# MCU.net
KiCad netlist of a schematic drawn in Altium Designer
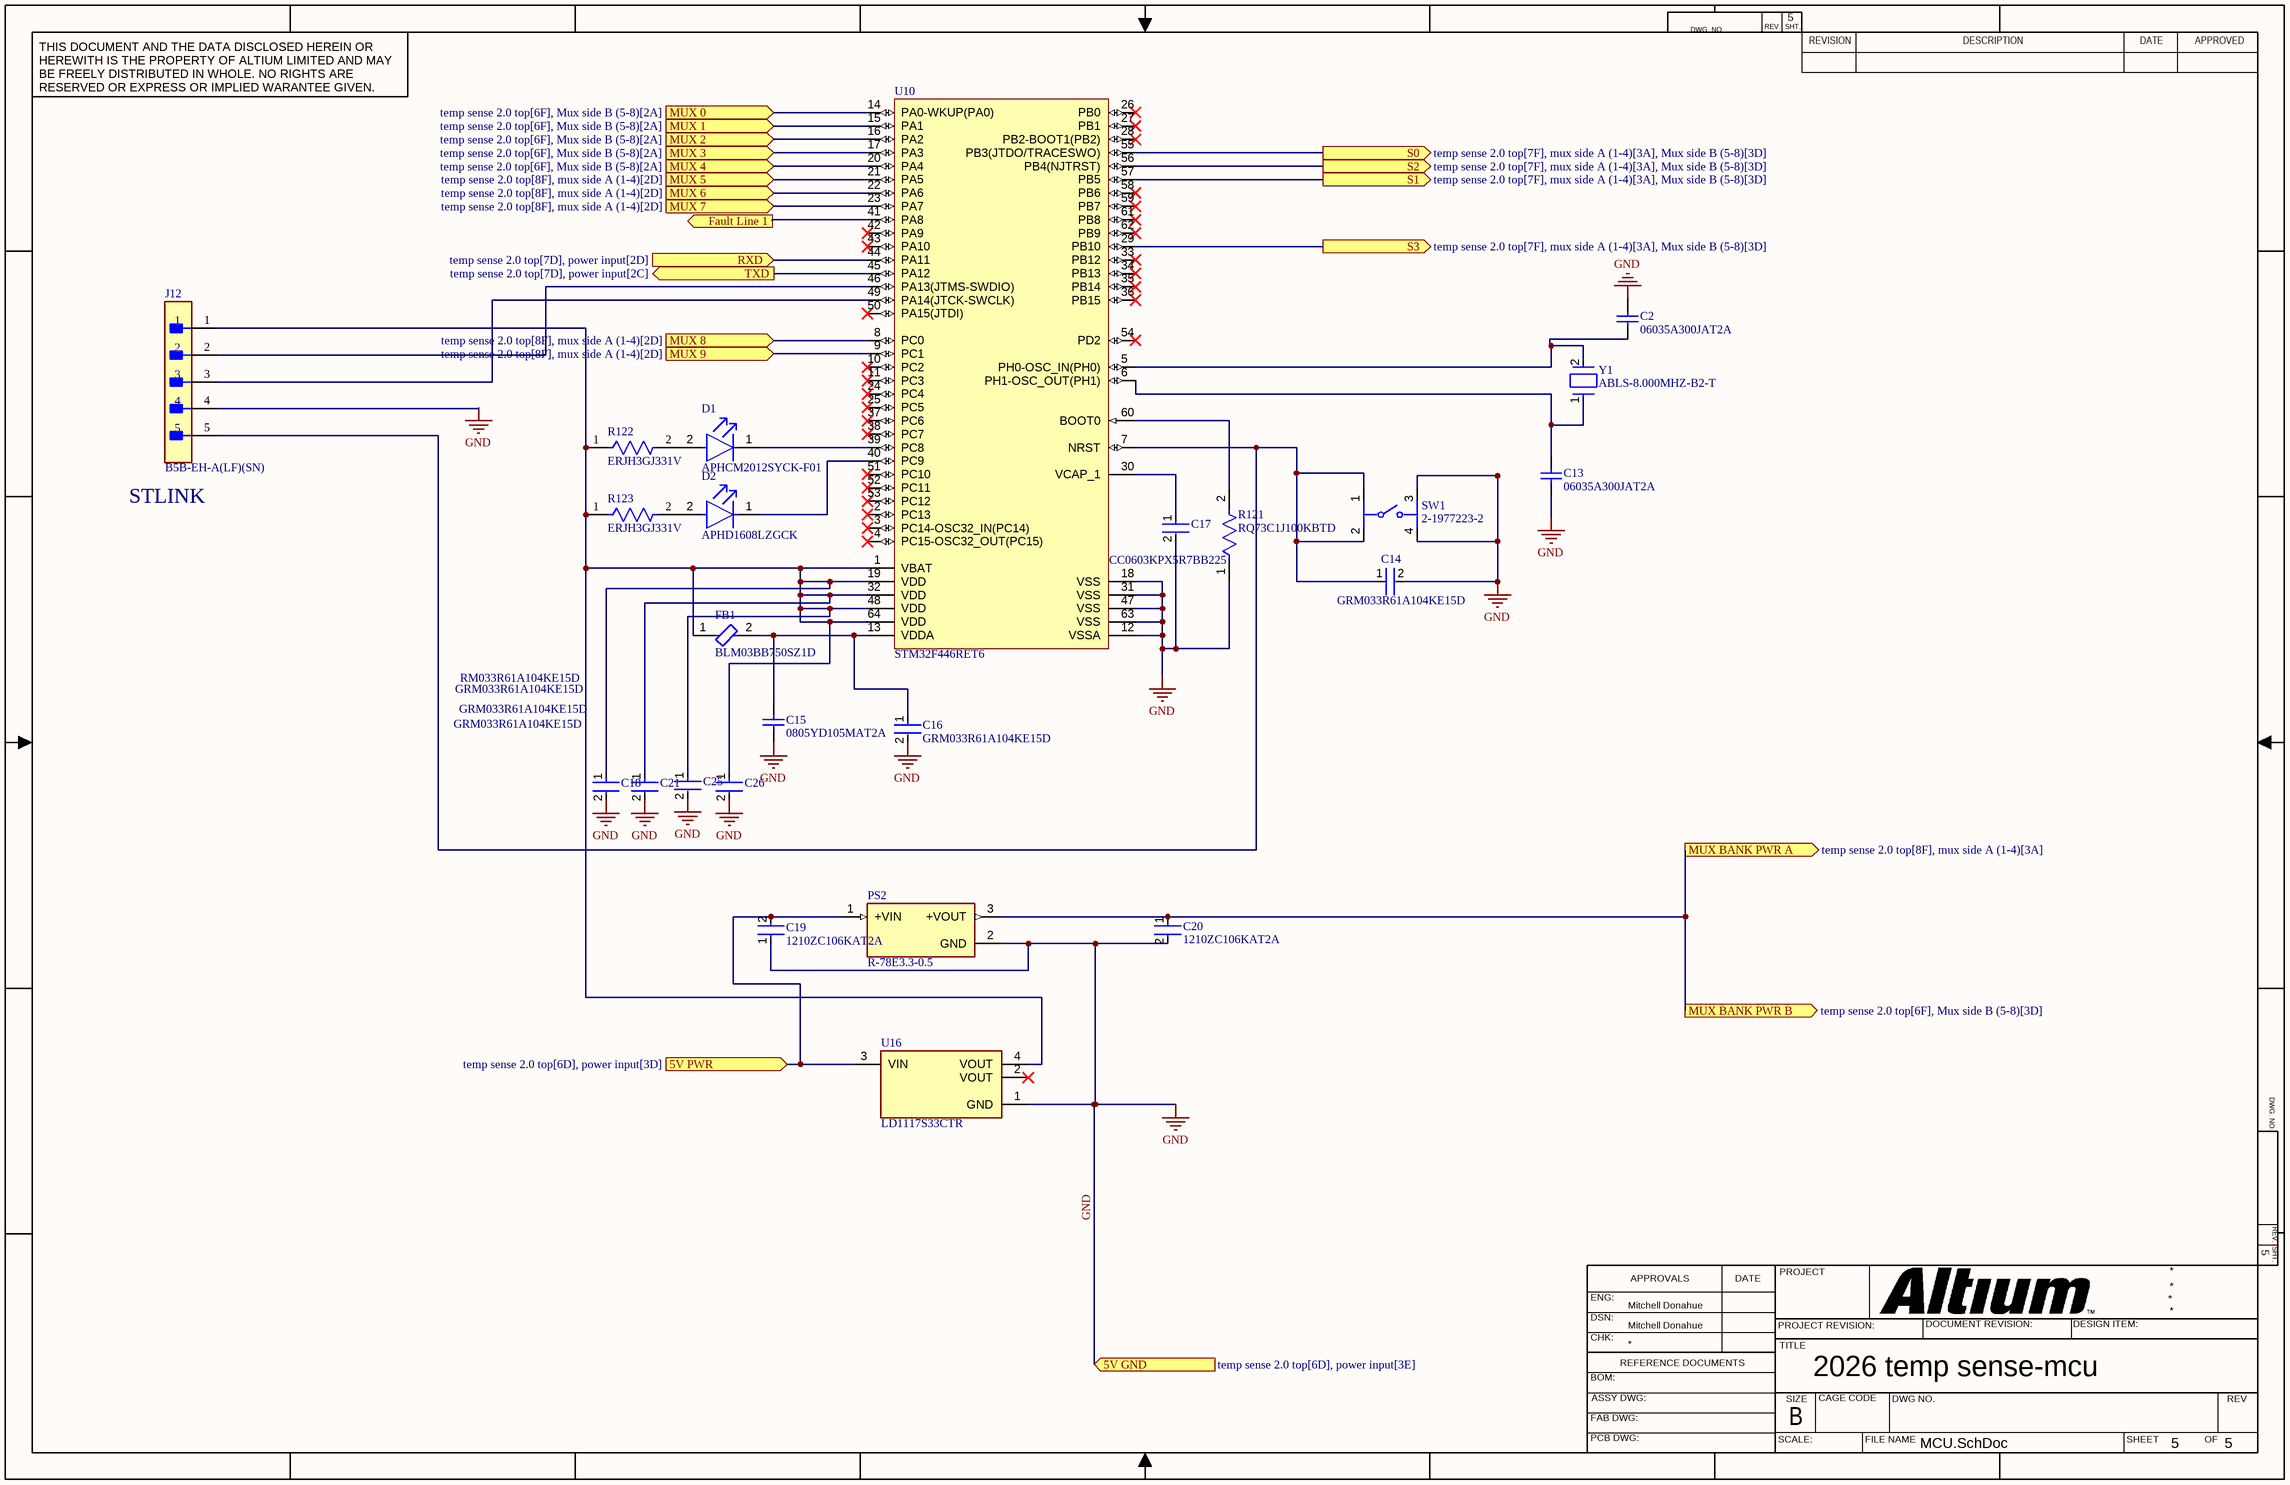
[diagram p0: MCU.SchDoc]

(export (version "E")
  (design (tool "Eeschema 10.0.6"))
  (components
    (comp (ref "C2")
      (value "06035A300JAT2A")
      (footprint "CAPC1608X90X35LL15T15")
      (fields (field (name "MANUFACTURER") "AVX Interconnect / Elco"))
      (libsource (lib "Altium Content Vault") (part "CAP"))
    )
    (comp (ref "C13")
      (value "06035A300JAT2A")
      (footprint "CAPC1608X90X35LL15T15")
      (fields (field (name "MANUFACTURER") "AVX Interconnect / Elco"))
      (libsource (lib "Altium Content Vault") (part "CAP"))
    )
    (comp (ref "C14")
      (value "GRM033R61A104KE15D")
      (footprint "FP-GRM033-0_03-IPC_C")
      (description "Chip Multilayer Ceramic Capacitors for General Purpose, 0201, 0.10uF, X5R, 15%, 10%, 10V")
      (fields (field (name "TOLERANCE") "10%") (field (name "VOLTAGE") "10V"))
      (libsource (lib "Altium Content Vault") (part "b4654b650e69147ec39a6b967a45e02"))
    )
    (comp (ref "C15")
      (value "0805YD105MAT2A")
      (footprint "CAPC2013X140X50NL20T25")
      (fields (field (name "MANUFACTURER") "AVX Interconnect / Elco"))
      (libsource (lib "Altium Content Vault") (part "CAP"))
    )
    (comp (ref "C16")
      (value "GRM033R61A104KE15D")
      (footprint "FP-GRM033-0_03-IPC_C")
      (description "Chip Multilayer Ceramic Capacitors for General Purpose, 0201, 0.10uF, X5R, 15%, 10%, 10V")
      (fields (field (name "TOLERANCE") "10%") (field (name "VOLTAGE") "10V"))
      (libsource (lib "Altium Content Vault") (part "b4654b650e69147ec39a6b967a45e02"))
    )
    (comp (ref "C17")
      (value "CC0603KPX5R7BB225")
      (footprint "FP-CC0603-DA-MFG")
      (description "CC0603 2.2 uF X5R 10.00% 16 V")
      (fields
        (field (name "MANUFACTURER") "YAGEO")
        (field (name "OCTOPART") "https://octopart.com/cc0603kpx5r7bb225-yageo-91091799")
      )
      (libsource (lib "Altium Content Vault") (part "11868f565c42a9108669ba33697ecf6"))
    )
    (comp (ref "C18")
      (value "GRM033R61A104KE15D")
      (footprint "FP-GRM033-0_03-IPC_C")
      (description "Chip Multilayer Ceramic Capacitors for General Purpose, 0201, 0.10uF, X5R, 15%, 10%, 10V")
      (fields (field (name "TOLERANCE") "10%") (field (name "VOLTAGE") "10V"))
      (libsource (lib "Altium Content Vault") (part "b4654b650e69147ec39a6b967a45e02"))
    )
    (comp (ref "C19")
      (value "1210ZC106KAT2A")
      (footprint "FP-1210-L_3_3_0_4-W_2_5_0-IPC_A")
      (description "CAP CER 10UF 10V X7R 1210")
      (fields (field (name "VOLTAGE") "10V") (field (name "TOLERANCE") "10%"))
      (libsource (lib "Altium Content Vault") (part "b4654b650e69147ec39a6b967a45e02"))
    )
    (comp (ref "C20")
      (value "1210ZC106KAT2A")
      (footprint "FP-1210-L_3_3_0_4-W_2_5_0-IPC_A")
      (description "CAP CER 10UF 10V X7R 1210")
      (fields (field (name "VOLTAGE") "10V") (field (name "TOLERANCE") "10%"))
      (libsource (lib "Altium Content Vault") (part "b4654b650e69147ec39a6b967a45e02"))
    )
    (comp (ref "C21")
      (value "RM033R61A104KE15D")
      (footprint "FP-GRM033-0_03-IPC_C")
      (description "Chip Multilayer Ceramic Capacitors for General Purpose, 0201, 0.10uF, X5R, 15%, 10%, 10V")
      (fields (field (name "TOLERANCE") "10%") (field (name "VOLTAGE") "10V"))
      (libsource (lib "Altium Content Vault") (part "b4654b650e69147ec39a6b967a45e02"))
    )
    (comp (ref "C25")
      (value "GRM033R61A104KE15D")
      (footprint "FP-GRM033-0_03-IPC_C")
      (description "Chip Multilayer Ceramic Capacitors for General Purpose, 0201, 0.10uF, X5R, 15%, 10%, 10V")
      (fields (field (name "TOLERANCE") "10%") (field (name "VOLTAGE") "10V"))
      (libsource (lib "Altium Content Vault") (part "b4654b650e69147ec39a6b967a45e02"))
    )
    (comp (ref "C26")
      (value "GRM033R61A104KE15D")
      (footprint "FP-GRM033-0_03-IPC_C")
      (description "Chip Multilayer Ceramic Capacitors for General Purpose, 0201, 0.10uF, X5R, 15%, 10%, 10V")
      (fields (field (name "TOLERANCE") "10%") (field (name "VOLTAGE") "10V"))
      (libsource (lib "Altium Content Vault") (part "b4654b650e69147ec39a6b967a45e02"))
    )
    (comp (ref "D1")
      (value "APHCM2012SYCK-F01")
      (footprint "FP-APHCM2012SYCK-F01-MFG")
      (description "LED YELLOW CLEAR CHIP SMD")
      (libsource (lib "Altium Content Vault") (part "8706943c75ba83719d021d2fdc84c58"))
    )
    (comp (ref "D2")
      (value "APHD1608LZGCK")
      (footprint "FP-APHD1608LZGCK-MFG")
      (description "LED GREEN CLEAR 1608 SMD")
      (libsource (lib "Altium Content Vault") (part "8706943c75ba83719d021d2fdc84c58"))
    )
    (comp (ref "FB1")
      (value "BLM03BB750SZ1D")
      (footprint "FP-BLM03-0_03-d0_3-IPC_C")
      (description "Ferrite Bead, 0201, 75Ω @ 100MHz, 25%, 1Ω, 200mA")
      (libsource (lib "Altium Content Vault") (part "5f30dd21d616792df468990f7003faa"))
    )
    (comp (ref "J12")
      (value "B5B-EH-A(LF)(SN)")
      (footprint "FP-B5B-EH-A_LF_SN-MFG")
      (description "CONN HEADER VERT 5POS 2.5MM")
      (libsource (lib "Altium Content Vault") (part "bf93c07fd2649a848d0ec8585582aab"))
    )
    (comp (ref "PS2")
      (value "R-78E3.3-0.5")
      (footprint "CONV_R-78E3.3-0.5")
      (description "0.5A DC/DC-Converter 'INNOLINE' SIP3 reg")
      (fields (field (name "DIGI-KEY_PART_NUMBER") "945-1661-5-ND") (field (name "MF") "Recom Power"))
      (libsource (lib "R-78E3.3-0.5") (part "R-78E3.3-0.5"))
    )
    (comp (ref "R121")
      (value "RQ73C1J100KBTD")
      (footprint "FP-RQ731J-IPC_C")
      (description "RQ73 0603 100KΩ  0.15W 10ppm/°C 0.1% 75V")
      (fields
        (field (name "OCTOPART") "https://octopart.com/rq73c1j100kbtd-te+connectivity-93908182")
        (field (name "TOLERANCE") "0.1%")
      )
      (libsource (lib "Altium Content Vault") (part "1029c3af85768c4190bb7ad29bc67b5"))
    )
    (comp (ref "R122")
      (value "ERJH3GJ331V")
      (footprint "FP-ERJH3G-MFG")
      (description "ERJH3GJ331V Res 330 Ohm 5% 1/8W 0603")
      (libsource (lib "Altium Content Vault") (part "1029c3af85768c4190bb7ad29bc67b5"))
    )
    (comp (ref "R123")
      (value "ERJH3GJ331V")
      (footprint "FP-ERJH3G-MFG")
      (description "ERJH3GJ331V Res 330 Ohm 5% 1/8W 0603")
      (libsource (lib "Altium Content Vault") (part "1029c3af85768c4190bb7ad29bc67b5"))
    )
    (comp (ref "SW1")
      (value "2-1977223-2")
      (footprint "FP-2-1977223-2-MFG")
      (description "SWITCH TACTILE SPST-NO 0.05A 24V")
      (libsource (lib "Altium Content Vault") (part "b8895f3f4cefb76e1819d2863dba89b"))
    )
    (comp (ref "U10")
      (value "STM32F446RET6")
      (footprint "STM-LQFP64_L")
      (libsource (lib "Altium Content Vault") (part "MC-ARM-STM32F446-LQFP64"))
    )
    (comp (ref "U16")
      (value "LD1117S33CTR")
      (footprint "FP-SOT-223-0046067_14-MFG")
      (description "IC REG LINEAR 3.3V 800MA SOT223")
      (libsource (lib "Altium Content Vault") (part "7818869c5c16ceab15634627166a29d"))
    )
    (comp (ref "Y1")
      (value "ABLS-8.000MHZ-B2-T")
      (footprint "FP-ABLS-MFG")
      (description "CRYSTAL 8.0000MHZ 18PF SMD")
      (fields (field (name "TOLERANCE") "20ppm"))
      (libsource (lib "Altium Content Vault") (part "c23a69dc6c9e2f18f2079038eb95dd1"))
    )
  )
  (nets
    (net (code "1") (name "/5V PWR") (class "Default")
      (node (ref "C19") (pin "2") (pinfunction "2_2") (pintype "passive"))
      (node (ref "PS2") (pin "1") (pinfunction "+VIN_1") (pintype "input"))
      (node (ref "U16") (pin "3") (pinfunction "VIN_3") (pintype "power_in"))
    )
    (net (code "2") (name "/Fault Line 1") (class "Default")
      (node (ref "U10") (pin "41") (pinfunction "PA8_41") (pintype "bidirectional"))
    )
    (net (code "3") (name "/MUX 0") (class "Default")
      (node (ref "U10") (pin "14") (pinfunction "PA0-WKUP(PA0)_14") (pintype "bidirectional"))
    )
    (net (code "4") (name "/MUX 1") (class "Default")
      (node (ref "U10") (pin "15") (pinfunction "PA1_15") (pintype "bidirectional"))
    )
    (net (code "5") (name "/MUX 2") (class "Default")
      (node (ref "U10") (pin "16") (pinfunction "PA2_16") (pintype "bidirectional"))
    )
    (net (code "6") (name "/MUX 3") (class "Default")
      (node (ref "U10") (pin "17") (pinfunction "PA3_17") (pintype "bidirectional"))
    )
    (net (code "7") (name "/MUX 4") (class "Default")
      (node (ref "U10") (pin "20") (pinfunction "PA4_20") (pintype "bidirectional"))
    )
    (net (code "8") (name "/MUX 5") (class "Default")
      (node (ref "U10") (pin "21") (pinfunction "PA5_21") (pintype "bidirectional"))
    )
    (net (code "9") (name "/MUX 6") (class "Default")
      (node (ref "U10") (pin "22") (pinfunction "PA6_22") (pintype "bidirectional"))
    )
    (net (code "10") (name "/MUX 7") (class "Default")
      (node (ref "U10") (pin "23") (pinfunction "PA7_23") (pintype "bidirectional"))
    )
    (net (code "11") (name "/MUX 8") (class "Default")
      (node (ref "U10") (pin "8") (pinfunction "PC0_8") (pintype "bidirectional"))
    )
    (net (code "12") (name "/MUX 9") (class "Default")
      (node (ref "U10") (pin "9") (pinfunction "PC1_9") (pintype "bidirectional"))
    )
    (net (code "13") (name "/MUX BANK PWR A") (class "Default")
      (node (ref "C20") (pin "1") (pinfunction "1_1") (pintype "passive"))
      (node (ref "PS2") (pin "3") (pinfunction "+VOUT_3") (pintype "output"))
    )
    (net (code "14") (name "/RXD") (class "Default")
      (node (ref "U10") (pin "44") (pinfunction "PA11_44") (pintype "bidirectional"))
    )
    (net (code "15") (name "/S0") (class "Default")
      (node (ref "U10") (pin "55") (pinfunction "PB3(JTDO/TRACESWO)_55") (pintype "bidirectional"))
    )
    (net (code "16") (name "/S1") (class "Default")
      (node (ref "U10") (pin "57") (pinfunction "PB5_57") (pintype "bidirectional"))
    )
    (net (code "17") (name "/S2") (class "Default")
      (node (ref "U10") (pin "56") (pinfunction "PB4(NJTRST)_56") (pintype "bidirectional"))
    )
    (net (code "18") (name "/S3") (class "Default")
      (node (ref "U10") (pin "29") (pinfunction "PB10_29") (pintype "bidirectional"))
    )
    (net (code "19") (name "/TXD") (class "Default")
      (node (ref "U10") (pin "45") (pinfunction "PA12_45") (pintype "bidirectional"))
    )
    (net (code "20") (name "GND") (class "Default")
      (node (ref "C13") (pin "1") (pinfunction "1_1") (pintype "passive"))
      (node (ref "C14") (pin "2") (pinfunction "2_2") (pintype "passive"))
      (node (ref "C15") (pin "1") (pinfunction "1_1") (pintype "passive"))
      (node (ref "C16") (pin "2") (pinfunction "2_2") (pintype "passive"))
      (node (ref "C17") (pin "2") (pinfunction "2_2") (pintype "passive"))
      (node (ref "C18") (pin "2") (pinfunction "2_2") (pintype "passive"))
      (node (ref "C19") (pin "1") (pinfunction "1_1") (pintype "passive"))
      (node (ref "C2") (pin "2") (pinfunction "2_2") (pintype "passive"))
      (node (ref "C20") (pin "2") (pinfunction "2_2") (pintype "passive"))
      (node (ref "C21") (pin "2") (pinfunction "2_2") (pintype "passive"))
      (node (ref "C25") (pin "2") (pinfunction "2_2") (pintype "passive"))
      (node (ref "C26") (pin "2") (pinfunction "2_2") (pintype "passive"))
      (node (ref "J12") (pin "4") (pinfunction "4_4") (pintype "passive"))
      (node (ref "PS2") (pin "2") (pinfunction "GND_2") (pintype "power_in"))
      (node (ref "R121") (pin "1") (pinfunction "1_1") (pintype "passive"))
      (node (ref "SW1") (pin "3") (pinfunction "3_3") (pintype "passive"))
      (node (ref "SW1") (pin "4") (pinfunction "4_4") (pintype "passive"))
      (node (ref "U10") (pin "12") (pinfunction "VSSA_12") (pintype "power_in"))
      (node (ref "U10") (pin "18") (pinfunction "VSS_18") (pintype "power_in"))
      (node (ref "U10") (pin "31") (pinfunction "VSS_31") (pintype "power_in"))
      (node (ref "U10") (pin "47") (pinfunction "VSS_47") (pintype "power_in"))
      (node (ref "U10") (pin "63") (pinfunction "VSS_63") (pintype "power_in"))
      (node (ref "U16") (pin "1") (pinfunction "GND_1") (pintype "power_in"))
    )
    (net (code "21") (name "Net-(D1-A)") (class "Default")
      (node (ref "D1") (pin "2") (pinfunction "A_2") (pintype "passive"))
      (node (ref "R122") (pin "2") (pinfunction "2_2") (pintype "passive"))
    )
    (net (code "22") (name "Net-(D1-C)") (class "Default")
      (node (ref "D1") (pin "1") (pinfunction "C_1") (pintype "passive"))
      (node (ref "U10") (pin "39") (pinfunction "PC8_39") (pintype "bidirectional"))
    )
    (net (code "23") (name "Net-(D2-A)") (class "Default")
      (node (ref "D2") (pin "2") (pinfunction "A_2") (pintype "passive"))
      (node (ref "R123") (pin "2") (pinfunction "2_2") (pintype "passive"))
    )
    (net (code "24") (name "Net-(D2-C)") (class "Default")
      (node (ref "D2") (pin "1") (pinfunction "C_1") (pintype "passive"))
      (node (ref "U10") (pin "40") (pinfunction "PC9_40") (pintype "bidirectional"))
    )
    (net (code "25") (name "Net-(U10-BOOT0)") (class "Default")
      (node (ref "R121") (pin "2") (pinfunction "2_2") (pintype "passive"))
      (node (ref "U10") (pin "60") (pinfunction "BOOT0_60") (pintype "input"))
    )
    (net (code "26") (name "Net-(U10-NRST)") (class "Default")
      (node (ref "C14") (pin "1") (pinfunction "1_1") (pintype "passive"))
      (node (ref "J12") (pin "5") (pinfunction "5_5") (pintype "passive"))
      (node (ref "SW1") (pin "1") (pinfunction "1_1") (pintype "passive"))
      (node (ref "SW1") (pin "2") (pinfunction "2_2") (pintype "passive"))
      (node (ref "U10") (pin "7") (pinfunction "NRST_7") (pintype "bidirectional"))
    )
    (net (code "27") (name "Net-(U10-PA13(JTMS-SWDIO))") (class "Default")
      (node (ref "J12") (pin "2") (pinfunction "2_2") (pintype "passive"))
      (node (ref "U10") (pin "46") (pinfunction "PA13(JTMS-SWDIO)_46") (pintype "bidirectional"))
    )
    (net (code "28") (name "Net-(U10-PA14(JTCK-SWCLK))") (class "Default")
      (node (ref "J12") (pin "3") (pinfunction "3_3") (pintype "passive"))
      (node (ref "U10") (pin "49") (pinfunction "PA14(JTCK-SWCLK)_49") (pintype "bidirectional"))
    )
    (net (code "29") (name "Net-(U10-PH0-OSC_IN(PH0))") (class "Default")
      (node (ref "C2") (pin "1") (pinfunction "1_1") (pintype "passive"))
      (node (ref "U10") (pin "5") (pinfunction "PH0-OSC_IN(PH0)_5") (pintype "bidirectional"))
      (node (ref "Y1") (pin "2") (pinfunction "2_2") (pintype "passive"))
    )
    (net (code "30") (name "Net-(U10-PH1-OSC_OUT(PH1))") (class "Default")
      (node (ref "C13") (pin "2") (pinfunction "2_2") (pintype "passive"))
      (node (ref "U10") (pin "6") (pinfunction "PH1-OSC_OUT(PH1)_6") (pintype "bidirectional"))
      (node (ref "Y1") (pin "1") (pinfunction "1_1") (pintype "passive"))
    )
    (net (code "31") (name "Net-(U10-VBAT)") (class "Default")
      (node (ref "C18") (pin "1") (pinfunction "1_1") (pintype "passive"))
      (node (ref "C21") (pin "1") (pinfunction "1_1") (pintype "passive"))
      (node (ref "C25") (pin "1") (pinfunction "1_1") (pintype "passive"))
      (node (ref "C26") (pin "1") (pinfunction "1_1") (pintype "passive"))
      (node (ref "FB1") (pin "1") (pinfunction "1_1") (pintype "passive"))
      (node (ref "J12") (pin "1") (pinfunction "1_1") (pintype "passive"))
      (node (ref "R122") (pin "1") (pinfunction "1_1") (pintype "passive"))
      (node (ref "R123") (pin "1") (pinfunction "1_1") (pintype "passive"))
      (node (ref "U10") (pin "1") (pinfunction "VBAT_1") (pintype "power_in"))
      (node (ref "U10") (pin "19") (pinfunction "VDD_19") (pintype "power_in"))
      (node (ref "U10") (pin "32") (pinfunction "VDD_32") (pintype "power_in"))
      (node (ref "U10") (pin "48") (pinfunction "VDD_48") (pintype "power_in"))
      (node (ref "U10") (pin "64") (pinfunction "VDD_64") (pintype "power_in"))
      (node (ref "U16") (pin "4") (pinfunction "VOUT_4") (pintype "power_in"))
    )
    (net (code "32") (name "Net-(U10-VCAP_1)") (class "Default")
      (node (ref "C17") (pin "1") (pinfunction "1_1") (pintype "passive"))
      (node (ref "U10") (pin "30") (pinfunction "VCAP_1_30") (pintype "passive"))
    )
    (net (code "33") (name "Net-(U10-VDDA)") (class "Default")
      (node (ref "C15") (pin "2") (pinfunction "2_2") (pintype "passive"))
      (node (ref "C16") (pin "1") (pinfunction "1_1") (pintype "passive"))
      (node (ref "FB1") (pin "2") (pinfunction "2_2") (pintype "passive"))
      (node (ref "U10") (pin "13") (pinfunction "VDDA_13") (pintype "power_in"))
    )
    (net (code "34") (name "unconnected-(U10-PA9-Pad42)") (class "Default")
      (node (ref "U10") (pin "42") (pinfunction "PA9_42") (pintype "bidirectional+no_connect"))
    )
    (net (code "35") (name "unconnected-(U10-PA10-Pad43)") (class "Default")
      (node (ref "U10") (pin "43") (pinfunction "PA10_43") (pintype "bidirectional+no_connect"))
    )
    (net (code "36") (name "unconnected-(U10-PA15(JTDI)-Pad50)") (class "Default")
      (node (ref "U10") (pin "50") (pinfunction "PA15(JTDI)_50") (pintype "bidirectional+no_connect"))
    )
    (net (code "37") (name "unconnected-(U10-PB0-Pad26)") (class "Default")
      (node (ref "U10") (pin "26") (pinfunction "PB0_26") (pintype "bidirectional+no_connect"))
    )
    (net (code "38") (name "unconnected-(U10-PB1-Pad27)") (class "Default")
      (node (ref "U10") (pin "27") (pinfunction "PB1_27") (pintype "bidirectional+no_connect"))
    )
    (net (code "39") (name "unconnected-(U10-PB2-BOOT1(PB2)-Pad28)") (class "Default")
      (node (ref "U10") (pin "28") (pinfunction "PB2-BOOT1(PB2)_28") (pintype "bidirectional+no_connect"))
    )
    (net (code "40") (name "unconnected-(U10-PB6-Pad58)") (class "Default")
      (node (ref "U10") (pin "58") (pinfunction "PB6_58") (pintype "bidirectional+no_connect"))
    )
    (net (code "41") (name "unconnected-(U10-PB7-Pad59)") (class "Default")
      (node (ref "U10") (pin "59") (pinfunction "PB7_59") (pintype "bidirectional+no_connect"))
    )
    (net (code "42") (name "unconnected-(U10-PB8-Pad61)") (class "Default")
      (node (ref "U10") (pin "61") (pinfunction "PB8_61") (pintype "bidirectional+no_connect"))
    )
    (net (code "43") (name "unconnected-(U10-PB9-Pad62)") (class "Default")
      (node (ref "U10") (pin "62") (pinfunction "PB9_62") (pintype "bidirectional+no_connect"))
    )
    (net (code "44") (name "unconnected-(U10-PB12-Pad33)") (class "Default")
      (node (ref "U10") (pin "33") (pinfunction "PB12_33") (pintype "bidirectional+no_connect"))
    )
    (net (code "45") (name "unconnected-(U10-PB13-Pad34)") (class "Default")
      (node (ref "U10") (pin "34") (pinfunction "PB13_34") (pintype "bidirectional+no_connect"))
    )
    (net (code "46") (name "unconnected-(U10-PB14-Pad35)") (class "Default")
      (node (ref "U10") (pin "35") (pinfunction "PB14_35") (pintype "bidirectional+no_connect"))
    )
    (net (code "47") (name "unconnected-(U10-PB15-Pad36)") (class "Default")
      (node (ref "U10") (pin "36") (pinfunction "PB15_36") (pintype "bidirectional+no_connect"))
    )
    (net (code "48") (name "unconnected-(U10-PC2-Pad10)") (class "Default")
      (node (ref "U10") (pin "10") (pinfunction "PC2_10") (pintype "bidirectional+no_connect"))
    )
    (net (code "49") (name "unconnected-(U10-PC3-Pad11)") (class "Default")
      (node (ref "U10") (pin "11") (pinfunction "PC3_11") (pintype "bidirectional+no_connect"))
    )
    (net (code "50") (name "unconnected-(U10-PC4-Pad24)") (class "Default")
      (node (ref "U10") (pin "24") (pinfunction "PC4_24") (pintype "bidirectional+no_connect"))
    )
    (net (code "51") (name "unconnected-(U10-PC5-Pad25)") (class "Default")
      (node (ref "U10") (pin "25") (pinfunction "PC5_25") (pintype "bidirectional+no_connect"))
    )
    (net (code "52") (name "unconnected-(U10-PC6-Pad37)") (class "Default")
      (node (ref "U10") (pin "37") (pinfunction "PC6_37") (pintype "bidirectional+no_connect"))
    )
    (net (code "53") (name "unconnected-(U10-PC7-Pad38)") (class "Default")
      (node (ref "U10") (pin "38") (pinfunction "PC7_38") (pintype "bidirectional+no_connect"))
    )
    (net (code "54") (name "unconnected-(U10-PC10-Pad51)") (class "Default")
      (node (ref "U10") (pin "51") (pinfunction "PC10_51") (pintype "bidirectional+no_connect"))
    )
    (net (code "55") (name "unconnected-(U10-PC11-Pad52)") (class "Default")
      (node (ref "U10") (pin "52") (pinfunction "PC11_52") (pintype "bidirectional+no_connect"))
    )
    (net (code "56") (name "unconnected-(U10-PC12-Pad53)") (class "Default")
      (node (ref "U10") (pin "53") (pinfunction "PC12_53") (pintype "bidirectional+no_connect"))
    )
    (net (code "57") (name "unconnected-(U10-PC13-Pad2)") (class "Default")
      (node (ref "U10") (pin "2") (pinfunction "PC13_2") (pintype "bidirectional+no_connect"))
    )
    (net (code "58") (name "unconnected-(U10-PC14-OSC32_IN(PC14)-Pad3)") (class "Default")
      (node (ref "U10") (pin "3") (pinfunction "PC14-OSC32_IN(PC14)_3") (pintype "bidirectional+no_connect"))
    )
    (net (code "59") (name "unconnected-(U10-PC15-OSC32_OUT(PC15)-Pad4)") (class "Default")
      (node (ref "U10") (pin "4") (pinfunction "PC15-OSC32_OUT(PC15)_4") (pintype "bidirectional+no_connect"))
    )
    (net (code "60") (name "unconnected-(U10-PD2-Pad54)") (class "Default")
      (node (ref "U10") (pin "54") (pinfunction "PD2_54") (pintype "bidirectional+no_connect"))
    )
    (net (code "61") (name "unconnected-(U16-VOUT-Pad2)") (class "Default")
      (node (ref "U16") (pin "2") (pinfunction "VOUT_2") (pintype "power_in+no_connect"))
    )
  )
)
